# mosfet_smt_test.net
KiCad netlist of a schematic drawn in EAGLE
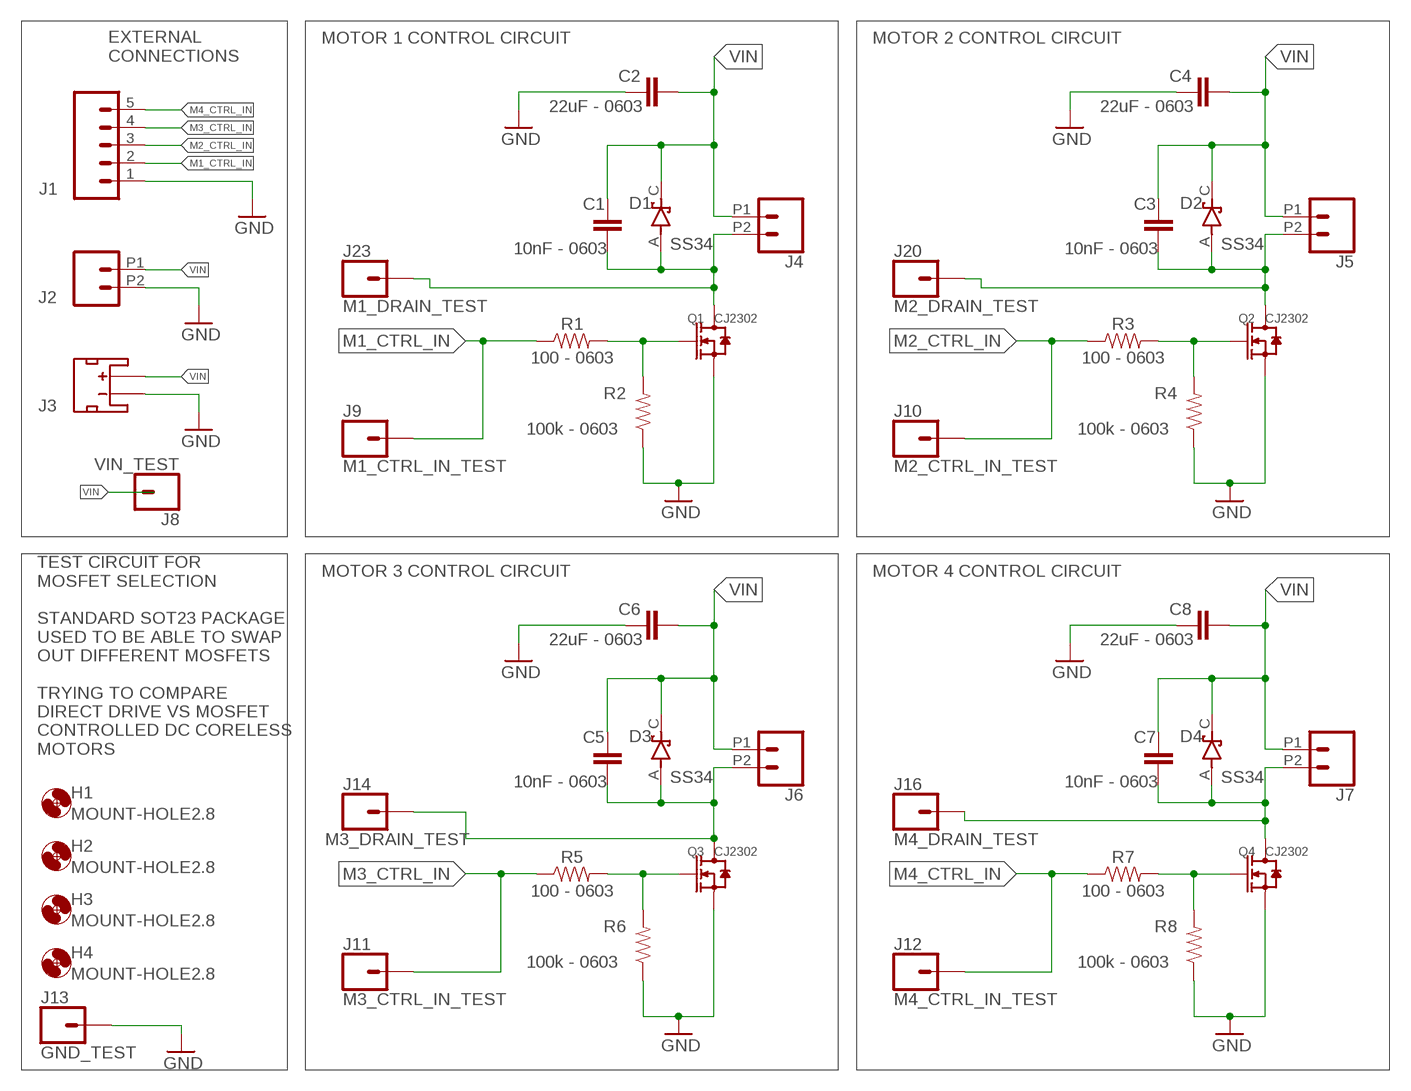
[diagram p0: schematic, sheet 1]

(export (version "E")
  (design (tool "Eeschema 10.0.6"))
  (components
    (comp (ref "C1")
      (value "10nF - 0603")
      (footprint "eagle-import:CAP_0603")
      (fields
        (field (name "DIGIKEY_PART_NUMBER") "311-1049-2-ND")
        (field (name "MANUFACTURER") "Yageo")
        (field (name "MPN") "CC0603CRNPO9BN1R0")
        (field (name "CREATED_BY") "PCBLayout.com")
      )
      (libsource (lib "eagle-import") (part "CC0603CRNPO9BN1R0"))
    )
    (comp (ref "C2")
      (value "22uF - 0603")
      (footprint "eagle-import:CAP_0603")
      (fields
        (field (name "DIGIKEY_PART_NUMBER") "311-1049-2-ND")
        (field (name "MANUFACTURER") "Yageo")
        (field (name "MPN") "CC0603CRNPO9BN1R0")
        (field (name "CREATED_BY") "PCBLayout.com")
      )
      (libsource (lib "eagle-import") (part "CC0603CRNPO9BN1R0"))
    )
    (comp (ref "C3")
      (value "10nF - 0603")
      (footprint "eagle-import:CAP_0603")
      (fields
        (field (name "DIGIKEY_PART_NUMBER") "311-1049-2-ND")
        (field (name "MANUFACTURER") "Yageo")
        (field (name "MPN") "CC0603CRNPO9BN1R0")
        (field (name "CREATED_BY") "PCBLayout.com")
      )
      (libsource (lib "eagle-import") (part "CC0603CRNPO9BN1R0"))
    )
    (comp (ref "C4")
      (value "22uF - 0603")
      (footprint "eagle-import:CAP_0603")
      (fields
        (field (name "DIGIKEY_PART_NUMBER") "311-1049-2-ND")
        (field (name "MANUFACTURER") "Yageo")
        (field (name "MPN") "CC0603CRNPO9BN1R0")
        (field (name "CREATED_BY") "PCBLayout.com")
      )
      (libsource (lib "eagle-import") (part "CC0603CRNPO9BN1R0"))
    )
    (comp (ref "C5")
      (value "10nF - 0603")
      (footprint "eagle-import:CAP_0603")
      (fields
        (field (name "DIGIKEY_PART_NUMBER") "311-1049-2-ND")
        (field (name "MANUFACTURER") "Yageo")
        (field (name "MPN") "CC0603CRNPO9BN1R0")
        (field (name "CREATED_BY") "PCBLayout.com")
      )
      (libsource (lib "eagle-import") (part "CC0603CRNPO9BN1R0"))
    )
    (comp (ref "C6")
      (value "22uF - 0603")
      (footprint "eagle-import:CAP_0603")
      (fields
        (field (name "DIGIKEY_PART_NUMBER") "311-1049-2-ND")
        (field (name "MANUFACTURER") "Yageo")
        (field (name "MPN") "CC0603CRNPO9BN1R0")
        (field (name "CREATED_BY") "PCBLayout.com")
      )
      (libsource (lib "eagle-import") (part "CC0603CRNPO9BN1R0"))
    )
    (comp (ref "C7")
      (value "10nF - 0603")
      (footprint "eagle-import:CAP_0603")
      (fields
        (field (name "DIGIKEY_PART_NUMBER") "311-1049-2-ND")
        (field (name "MANUFACTURER") "Yageo")
        (field (name "MPN") "CC0603CRNPO9BN1R0")
        (field (name "CREATED_BY") "PCBLayout.com")
      )
      (libsource (lib "eagle-import") (part "CC0603CRNPO9BN1R0"))
    )
    (comp (ref "C8")
      (value "22uF - 0603")
      (footprint "eagle-import:CAP_0603")
      (fields
        (field (name "DIGIKEY_PART_NUMBER") "311-1049-2-ND")
        (field (name "MANUFACTURER") "Yageo")
        (field (name "MPN") "CC0603CRNPO9BN1R0")
        (field (name "CREATED_BY") "PCBLayout.com")
      )
      (libsource (lib "eagle-import") (part "CC0603CRNPO9BN1R0"))
    )
    (comp (ref "D1")
      (value "SS34")
      (footprint "eagle-import:DIOM7959X265N")
      (fields (field (name "MF") "ON Semiconductor"))
      (libsource (lib "eagle-import") (part "SS34"))
    )
    (comp (ref "D2")
      (value "SS34")
      (footprint "eagle-import:DIOM7959X265N")
      (fields (field (name "MF") "ON Semiconductor"))
      (libsource (lib "eagle-import") (part "SS34"))
    )
    (comp (ref "D3")
      (value "SS34")
      (footprint "eagle-import:DIOM7959X265N")
      (fields (field (name "MF") "ON Semiconductor"))
      (libsource (lib "eagle-import") (part "SS34"))
    )
    (comp (ref "D4")
      (value "SS34")
      (footprint "eagle-import:DIOM7959X265N")
      (fields (field (name "MF") "ON Semiconductor"))
      (libsource (lib "eagle-import") (part "SS34"))
    )
    (comp (ref "H1")
      (value "MOUNT-HOLE2.8")
      (footprint "eagle-import:2,8")
      (libsource (lib "eagle-import") (part "MOUNT-HOLE2.8"))
    )
    (comp (ref "H2")
      (value "MOUNT-HOLE2.8")
      (footprint "eagle-import:2,8")
      (libsource (lib "eagle-import") (part "MOUNT-HOLE2.8"))
    )
    (comp (ref "H3")
      (value "MOUNT-HOLE2.8")
      (footprint "eagle-import:2,8")
      (libsource (lib "eagle-import") (part "MOUNT-HOLE2.8"))
    )
    (comp (ref "H4")
      (value "MOUNT-HOLE2.8")
      (footprint "eagle-import:2,8")
      (libsource (lib "eagle-import") (part "MOUNT-HOLE2.8"))
    )
    (comp (ref "J1")
      (value "CONN_05")
      (footprint "eagle-import:1X05")
      (libsource (lib "eagle-import") (part "CONN_05"))
    )
    (comp (ref "J2")
      (value "CONN_022.54MM_SCREWTERM")
      (footprint "eagle-import:1X02_2.54_SCREWTERM")
      (libsource (lib "eagle-import") (part "CONN_022.54MM_SCREWTERM"))
    )
    (comp (ref "J3")
      (value "JST_2MM_MALE")
      (footprint "eagle-import:JST-2-SMD")
      (libsource (lib "eagle-import") (part "JST_2MM_MALE"))
    )
    (comp (ref "J4")
      (value "CONN_022.54MM_SCREWTERM")
      (footprint "eagle-import:1X02_2.54_SCREWTERM")
      (libsource (lib "eagle-import") (part "CONN_022.54MM_SCREWTERM"))
    )
    (comp (ref "J5")
      (value "CONN_022.54MM_SCREWTERM")
      (footprint "eagle-import:1X02_2.54_SCREWTERM")
      (libsource (lib "eagle-import") (part "CONN_022.54MM_SCREWTERM"))
    )
    (comp (ref "J6")
      (value "CONN_022.54MM_SCREWTERM")
      (footprint "eagle-import:1X02_2.54_SCREWTERM")
      (libsource (lib "eagle-import") (part "CONN_022.54MM_SCREWTERM"))
    )
    (comp (ref "J7")
      (value "CONN_022.54MM_SCREWTERM")
      (footprint "eagle-import:1X02_2.54_SCREWTERM")
      (libsource (lib "eagle-import") (part "CONN_022.54MM_SCREWTERM"))
    )
    (comp (ref "J8")
      (value "VIN_TEST")
      (footprint "eagle-import:1X01")
      (libsource (lib "eagle-import") (part "CONN_01"))
    )
    (comp (ref "J9")
      (value "M1_CTRL_IN_TEST")
      (footprint "eagle-import:1X01")
      (libsource (lib "eagle-import") (part "CONN_01"))
    )
    (comp (ref "J10")
      (value "M2_CTRL_IN_TEST")
      (footprint "eagle-import:1X01")
      (libsource (lib "eagle-import") (part "CONN_01"))
    )
    (comp (ref "J11")
      (value "M3_CTRL_IN_TEST")
      (footprint "eagle-import:1X01")
      (libsource (lib "eagle-import") (part "CONN_01"))
    )
    (comp (ref "J12")
      (value "M4_CTRL_IN_TEST")
      (footprint "eagle-import:1X01")
      (libsource (lib "eagle-import") (part "CONN_01"))
    )
    (comp (ref "J13")
      (value "GND_TEST")
      (footprint "eagle-import:1X01")
      (libsource (lib "eagle-import") (part "CONN_01"))
    )
    (comp (ref "J14")
      (value "M3_DRAIN_TEST")
      (footprint "eagle-import:1X01")
      (libsource (lib "eagle-import") (part "CONN_01"))
    )
    (comp (ref "J16")
      (value "M4_DRAIN_TEST")
      (footprint "eagle-import:1X01")
      (libsource (lib "eagle-import") (part "CONN_01"))
    )
    (comp (ref "J20")
      (value "M2_DRAIN_TEST")
      (footprint "eagle-import:1X01")
      (libsource (lib "eagle-import") (part "CONN_01"))
    )
    (comp (ref "J23")
      (value "M1_DRAIN_TEST")
      (footprint "eagle-import:1X01")
      (libsource (lib "eagle-import") (part "CONN_01"))
    )
    (comp (ref "Q1")
      (value "CJ2302")
      (footprint "eagle-import:SOT-23")
      (libsource (lib "eagle-import") (part "SMD-MOSFET-N-CH-20V-2.1A-CJ2302(SOT-23)"))
    )
    (comp (ref "Q2")
      (value "CJ2302")
      (footprint "eagle-import:SOT-23")
      (libsource (lib "eagle-import") (part "SMD-MOSFET-N-CH-20V-2.1A-CJ2302(SOT-23)"))
    )
    (comp (ref "Q3")
      (value "CJ2302")
      (footprint "eagle-import:SOT-23")
      (libsource (lib "eagle-import") (part "SMD-MOSFET-N-CH-20V-2.1A-CJ2302(SOT-23)"))
    )
    (comp (ref "Q4")
      (value "CJ2302")
      (footprint "eagle-import:SOT-23")
      (libsource (lib "eagle-import") (part "SMD-MOSFET-N-CH-20V-2.1A-CJ2302(SOT-23)"))
    )
    (comp (ref "R1")
      (value "100 - 0603")
      (footprint "eagle-import:0603")
      (libsource (lib "eagle-import") (part "0OHM-0603-1/10W-5%"))
    )
    (comp (ref "R2")
      (value "100k - 0603")
      (footprint "eagle-import:0603")
      (libsource (lib "eagle-import") (part "0OHM-0603-1/10W-5%"))
    )
    (comp (ref "R3")
      (value "100 - 0603")
      (footprint "eagle-import:0603")
      (libsource (lib "eagle-import") (part "0OHM-0603-1/10W-5%"))
    )
    (comp (ref "R4")
      (value "100k - 0603")
      (footprint "eagle-import:0603")
      (libsource (lib "eagle-import") (part "0OHM-0603-1/10W-5%"))
    )
    (comp (ref "R5")
      (value "100 - 0603")
      (footprint "eagle-import:0603")
      (libsource (lib "eagle-import") (part "0OHM-0603-1/10W-5%"))
    )
    (comp (ref "R6")
      (value "100k - 0603")
      (footprint "eagle-import:0603")
      (libsource (lib "eagle-import") (part "0OHM-0603-1/10W-5%"))
    )
    (comp (ref "R7")
      (value "100 - 0603")
      (footprint "eagle-import:0603")
      (libsource (lib "eagle-import") (part "0OHM-0603-1/10W-5%"))
    )
    (comp (ref "R8")
      (value "100k - 0603")
      (footprint "eagle-import:0603")
      (libsource (lib "eagle-import") (part "0OHM-0603-1/10W-5%"))
    )
  )
  (nets
    (net (code "1") (name "GND") (class "Default")
      (node (ref "C2") (pin "2") (pinfunction "2_2") (pintype "passive"))
      (node (ref "C4") (pin "2") (pinfunction "2_2") (pintype "passive"))
      (node (ref "C6") (pin "2") (pinfunction "2_2") (pintype "passive"))
      (node (ref "C8") (pin "2") (pinfunction "2_2") (pintype "passive"))
      (node (ref "J1") (pin "1") (pinfunction "1_1") (pintype "passive"))
      (node (ref "J13") (pin "1") (pinfunction "1_1") (pintype "passive"))
      (node (ref "J2") (pin "P2") (pinfunction "2_P2") (pintype "passive"))
      (node (ref "J3") (pin "1") (pinfunction "-_1") (pintype "bidirectional"))
      (node (ref "Q1") (pin "2") (pinfunction "S_2") (pintype "passive"))
      (node (ref "Q2") (pin "2") (pinfunction "S_2") (pintype "passive"))
      (node (ref "Q3") (pin "2") (pinfunction "S_2") (pintype "passive"))
      (node (ref "Q4") (pin "2") (pinfunction "S_2") (pintype "passive"))
      (node (ref "R2") (pin "1") (pinfunction "1_1") (pintype "passive"))
      (node (ref "R4") (pin "1") (pinfunction "1_1") (pintype "passive"))
      (node (ref "R6") (pin "1") (pinfunction "1_1") (pintype "passive"))
      (node (ref "R8") (pin "1") (pinfunction "1_1") (pintype "passive"))
    )
    (net (code "2") (name "M1_CTRL_IN") (class "Default")
      (node (ref "J1") (pin "2") (pinfunction "2_2") (pintype "passive"))
      (node (ref "J9") (pin "1") (pinfunction "1_1") (pintype "passive"))
      (node (ref "R1") (pin "1") (pinfunction "1_1") (pintype "passive"))
    )
    (net (code "3") (name "M2_CTRL_IN") (class "Default")
      (node (ref "J1") (pin "3") (pinfunction "3_3") (pintype "passive"))
      (node (ref "J10") (pin "1") (pinfunction "1_1") (pintype "passive"))
      (node (ref "R3") (pin "1") (pinfunction "1_1") (pintype "passive"))
    )
    (net (code "4") (name "M3_CTRL_IN") (class "Default")
      (node (ref "J1") (pin "4") (pinfunction "4_4") (pintype "passive"))
      (node (ref "J11") (pin "1") (pinfunction "1_1") (pintype "passive"))
      (node (ref "R5") (pin "1") (pinfunction "1_1") (pintype "passive"))
    )
    (net (code "5") (name "M4_CTRL_IN") (class "Default")
      (node (ref "J1") (pin "5") (pinfunction "5_5") (pintype "passive"))
      (node (ref "J12") (pin "1") (pinfunction "1_1") (pintype "passive"))
      (node (ref "R7") (pin "1") (pinfunction "1_1") (pintype "passive"))
    )
    (net (code "6") (name "Net-(J4-2)") (class "Default")
      (node (ref "C1") (pin "2") (pinfunction "2_2") (pintype "passive"))
      (node (ref "D1") (pin "A") (pinfunction "A_A") (pintype "passive"))
      (node (ref "J23") (pin "1") (pinfunction "1_1") (pintype "passive"))
      (node (ref "J4") (pin "P2") (pinfunction "2_P2") (pintype "passive"))
      (node (ref "Q1") (pin "3") (pinfunction "D_3") (pintype "passive"))
    )
    (net (code "7") (name "Net-(J5-2)") (class "Default")
      (node (ref "C3") (pin "2") (pinfunction "2_2") (pintype "passive"))
      (node (ref "D2") (pin "A") (pinfunction "A_A") (pintype "passive"))
      (node (ref "J20") (pin "1") (pinfunction "1_1") (pintype "passive"))
      (node (ref "J5") (pin "P2") (pinfunction "2_P2") (pintype "passive"))
      (node (ref "Q2") (pin "3") (pinfunction "D_3") (pintype "passive"))
    )
    (net (code "8") (name "Net-(J6-2)") (class "Default")
      (node (ref "C5") (pin "2") (pinfunction "2_2") (pintype "passive"))
      (node (ref "D3") (pin "A") (pinfunction "A_A") (pintype "passive"))
      (node (ref "J14") (pin "1") (pinfunction "1_1") (pintype "passive"))
      (node (ref "J6") (pin "P2") (pinfunction "2_P2") (pintype "passive"))
      (node (ref "Q3") (pin "3") (pinfunction "D_3") (pintype "passive"))
    )
    (net (code "9") (name "Net-(J7-2)") (class "Default")
      (node (ref "C7") (pin "2") (pinfunction "2_2") (pintype "passive"))
      (node (ref "D4") (pin "A") (pinfunction "A_A") (pintype "passive"))
      (node (ref "J16") (pin "1") (pinfunction "1_1") (pintype "passive"))
      (node (ref "J7") (pin "P2") (pinfunction "2_P2") (pintype "passive"))
      (node (ref "Q4") (pin "3") (pinfunction "D_3") (pintype "passive"))
    )
    (net (code "10") (name "Net-(Q1-G)") (class "Default")
      (node (ref "Q1") (pin "1") (pinfunction "G_1") (pintype "passive"))
      (node (ref "R1") (pin "2") (pinfunction "2_2") (pintype "passive"))
      (node (ref "R2") (pin "2") (pinfunction "2_2") (pintype "passive"))
    )
    (net (code "11") (name "Net-(Q2-G)") (class "Default")
      (node (ref "Q2") (pin "1") (pinfunction "G_1") (pintype "passive"))
      (node (ref "R3") (pin "2") (pinfunction "2_2") (pintype "passive"))
      (node (ref "R4") (pin "2") (pinfunction "2_2") (pintype "passive"))
    )
    (net (code "12") (name "Net-(Q3-G)") (class "Default")
      (node (ref "Q3") (pin "1") (pinfunction "G_1") (pintype "passive"))
      (node (ref "R5") (pin "2") (pinfunction "2_2") (pintype "passive"))
      (node (ref "R6") (pin "2") (pinfunction "2_2") (pintype "passive"))
    )
    (net (code "13") (name "Net-(Q4-G)") (class "Default")
      (node (ref "Q4") (pin "1") (pinfunction "G_1") (pintype "passive"))
      (node (ref "R7") (pin "2") (pinfunction "2_2") (pintype "passive"))
      (node (ref "R8") (pin "2") (pinfunction "2_2") (pintype "passive"))
    )
    (net (code "14") (name "VIN") (class "Default")
      (node (ref "C1") (pin "1") (pinfunction "1_1") (pintype "passive"))
      (node (ref "C2") (pin "1") (pinfunction "1_1") (pintype "passive"))
      (node (ref "C3") (pin "1") (pinfunction "1_1") (pintype "passive"))
      (node (ref "C4") (pin "1") (pinfunction "1_1") (pintype "passive"))
      (node (ref "C5") (pin "1") (pinfunction "1_1") (pintype "passive"))
      (node (ref "C6") (pin "1") (pinfunction "1_1") (pintype "passive"))
      (node (ref "C7") (pin "1") (pinfunction "1_1") (pintype "passive"))
      (node (ref "C8") (pin "1") (pinfunction "1_1") (pintype "passive"))
      (node (ref "D1") (pin "C") (pinfunction "K_C") (pintype "passive"))
      (node (ref "D2") (pin "C") (pinfunction "K_C") (pintype "passive"))
      (node (ref "D3") (pin "C") (pinfunction "K_C") (pintype "passive"))
      (node (ref "D4") (pin "C") (pinfunction "K_C") (pintype "passive"))
      (node (ref "J2") (pin "P1") (pinfunction "1_P1") (pintype "passive"))
      (node (ref "J3") (pin "2") (pinfunction "+_2") (pintype "bidirectional"))
      (node (ref "J4") (pin "P1") (pinfunction "1_P1") (pintype "passive"))
      (node (ref "J5") (pin "P1") (pinfunction "1_P1") (pintype "passive"))
      (node (ref "J6") (pin "P1") (pinfunction "1_P1") (pintype "passive"))
      (node (ref "J7") (pin "P1") (pinfunction "1_P1") (pintype "passive"))
      (node (ref "J8") (pin "1") (pinfunction "1_1") (pintype "passive"))
    )
    (net (code "15") (name "unconnected-(J3-PAD1-PadNC1)") (class "Default")
      (node (ref "J3") (pin "NC1") (pinfunction "PAD1_NC1") (pintype "bidirectional"))
    )
    (net (code "16") (name "unconnected-(J3-PAD2-PadNC2)") (class "Default")
      (node (ref "J3") (pin "NC2") (pinfunction "PAD2_NC2") (pintype "bidirectional"))
    )
  )
)
